# untitled.net
KiCad netlist of a schematic drawn in EAGLE
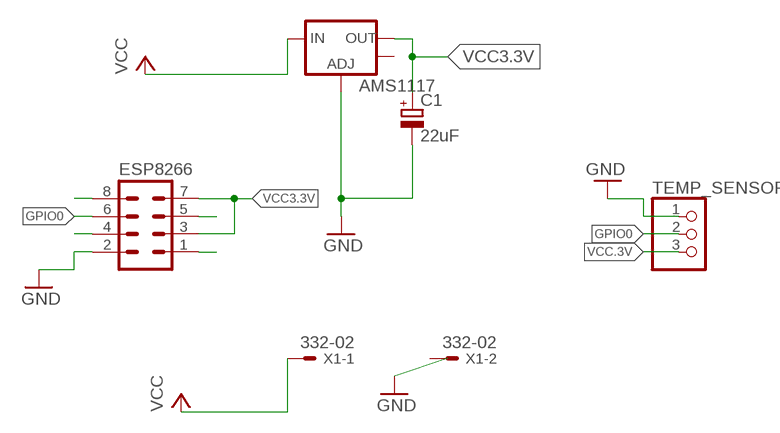
[diagram p0: schematic, sheet 1]

(export (version "E")
  (design (tool "Eeschema 10.0.6"))
  (components
    (comp (ref "AMS1117")
      (value "V_REG_LM1117SOT223")
      (footprint "eagle-import:SOT223")
      (libsource (lib "eagle-import") (part "V_REG_LM1117SOT223"))
    )
    (comp (ref "C1")
      (value "22uF")
      (footprint "eagle-import:E1,8-4")
      (libsource (lib "eagle-import") (part "CPOL-EUE1.8-4"))
    )
    (comp (ref "ESP8266")
      (value "MA04-2")
      (footprint "eagle-import:MA04-2")
      (libsource (lib "eagle-import") (part "MA04-2"))
    )
    (comp (ref "TEMP_SENSOR")
      (value "PINHD-1X3")
      (footprint "eagle-import:1X03")
      (libsource (lib "eagle-import") (part "PINHD-1X3"))
    )
    (comp (ref "X1")
      (value "332-02")
      (footprint "eagle-import:332-02")
      (libsource (lib "eagle-import") (part "332-02"))
    )
  )
  (nets
    (net (code "1") (name "GND") (class "Default")
      (node (ref "AMS1117") (pin "1") (pinfunction "ADJ_1") (pintype "input"))
      (node (ref "C1") (pin "-") (pinfunction "-_-") (pintype "passive"))
      (node (ref "ESP8266") (pin "2") (pinfunction "2_2") (pintype "passive"))
      (node (ref "TEMP_SENSOR") (pin "1") (pinfunction "1_1") (pintype "passive"))
    )
    (net (code "2") (name "GPIO0") (class "Default")
      (node (ref "ESP8266") (pin "6") (pinfunction "6_6") (pintype "passive"))
      (node (ref "TEMP_SENSOR") (pin "2") (pinfunction "2_2") (pintype "passive"))
    )
    (net (code "3") (name "VCC") (class "Default")
      (node (ref "AMS1117") (pin "3") (pinfunction "IN_3") (pintype "input"))
      (node (ref "X1") (pin "1") (pinfunction "S_1") (pintype "passive"))
    )
    (net (code "4") (name "VCC.3V") (class "Default")
      (node (ref "TEMP_SENSOR") (pin "3") (pinfunction "3_3") (pintype "passive"))
    )
    (net (code "5") (name "VCC3.3V") (class "Default")
      (node (ref "AMS1117") (pin "2") (pinfunction "OUT_2") (pintype "output"))
      (node (ref "C1") (pin "+") (pinfunction "+_+") (pintype "passive"))
      (node (ref "ESP8266") (pin "3") (pinfunction "3_3") (pintype "passive"))
      (node (ref "ESP8266") (pin "7") (pinfunction "7_7") (pintype "passive"))
    )
    (net (code "6") (name "unconnected-(AMS1117-OUT-Pad4)") (class "Default")
      (node (ref "AMS1117") (pin "4") (pinfunction "OUT_4") (pintype "output"))
    )
    (net (code "7") (name "unconnected-(ESP8266-Pad1)") (class "Default")
      (node (ref "ESP8266") (pin "1") (pinfunction "1_1") (pintype "passive"))
    )
    (net (code "8") (name "unconnected-(ESP8266-Pad4)") (class "Default")
      (node (ref "ESP8266") (pin "4") (pinfunction "4_4") (pintype "passive"))
    )
    (net (code "9") (name "unconnected-(ESP8266-Pad5)") (class "Default")
      (node (ref "ESP8266") (pin "5") (pinfunction "5_5") (pintype "passive"))
    )
    (net (code "10") (name "unconnected-(ESP8266-Pad8)") (class "Default")
      (node (ref "ESP8266") (pin "8") (pinfunction "8_8") (pintype "passive"))
    )
    (net (code "11") (name "unconnected-(X1B-S-Pad2)") (class "Default")
      (node (ref "X1") (pin "2") (pinfunction "S_2") (pintype "passive"))
    )
  )
)
